# Flipper-Proto.net
KiCad netlist of a schematic drawn in EAGLE
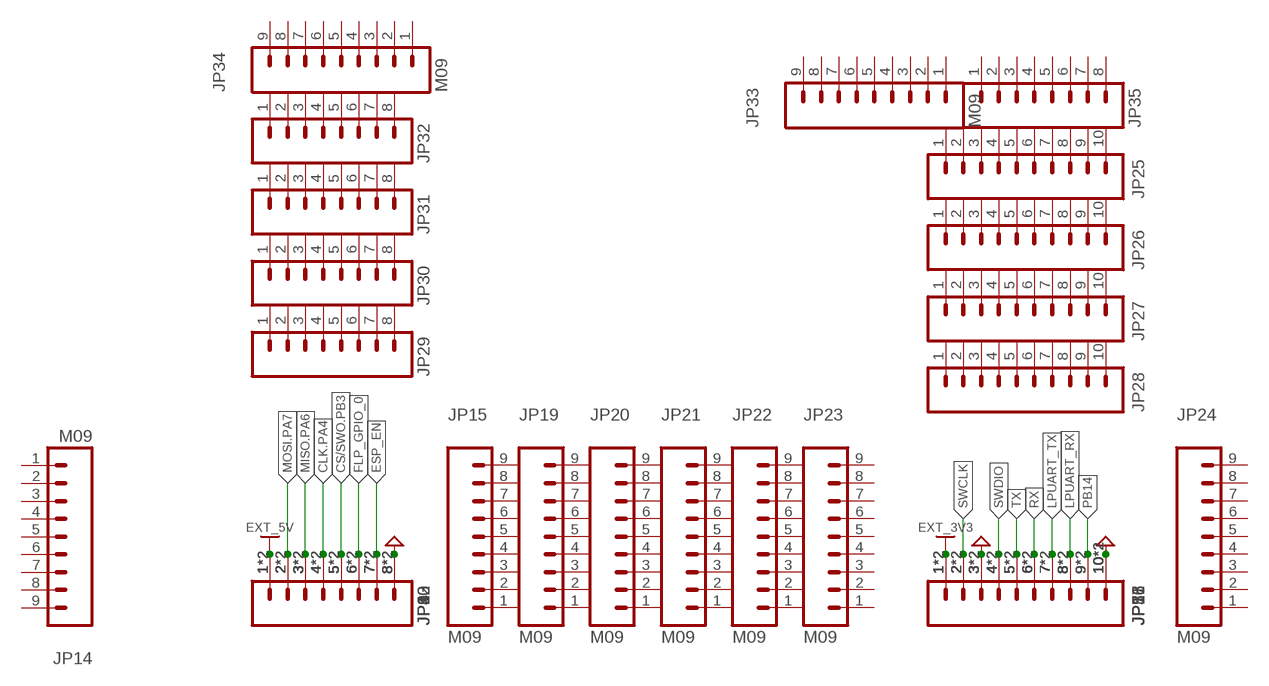
[diagram p0: schematic, sheet 1]

(export (version "E")
  (design (tool "Eeschema 10.0.6"))
  (components
    (comp (ref "JP1")
      (value "M10\"")
      (footprint "eagle-import:1X10")
      (libsource (lib "eagle-import") (part "M10{dblquote}"))
    )
    (comp (ref "JP2")
      (value "M08SMD-COMBO")
      (footprint "eagle-import:1X08_SMD_COMBINED")
      (libsource (lib "eagle-import") (part "M08SMD-COMBO"))
    )
    (comp (ref "JP3")
      (value "M08SMD-COMBO")
      (footprint "eagle-import:1X08_SMD_COMBINED")
      (libsource (lib "eagle-import") (part "M08SMD-COMBO"))
    )
    (comp (ref "JP4")
      (value "M08SMD-COMBO")
      (footprint "eagle-import:1X08_SMD_COMBINED")
      (libsource (lib "eagle-import") (part "M08SMD-COMBO"))
    )
    (comp (ref "JP5")
      (value "M10COMBINED")
      (footprint "eagle-import:1X10_SMD_COMBINED")
      (libsource (lib "eagle-import") (part "M10COMBINED"))
    )
    (comp (ref "JP6")
      (value "M081X08")
      (footprint "eagle-import:1X08")
      (libsource (lib "eagle-import") (part "M081X08"))
    )
    (comp (ref "JP7")
      (value "M10COMBINED")
      (footprint "eagle-import:1X10_SMD_COMBINED")
      (libsource (lib "eagle-import") (part "M10COMBINED"))
    )
    (comp (ref "JP8")
      (value "M10COMBINED")
      (footprint "eagle-import:1X10_SMD_COMBINED")
      (libsource (lib "eagle-import") (part "M10COMBINED"))
    )
    (comp (ref "JP9")
      (value "M081X08")
      (footprint "eagle-import:1X08")
      (libsource (lib "eagle-import") (part "M081X08"))
    )
    (comp (ref "JP10")
      (value "M081X08")
      (footprint "eagle-import:1X08")
      (libsource (lib "eagle-import") (part "M081X08"))
    )
    (comp (ref "JP11")
      (value "M10\"")
      (footprint "eagle-import:1X10")
      (libsource (lib "eagle-import") (part "M10{dblquote}"))
    )
    (comp (ref "JP12")
      (value "M081X08")
      (footprint "eagle-import:1X08")
      (libsource (lib "eagle-import") (part "M081X08"))
    )
    (comp (ref "JP13")
      (value "M081X08")
      (footprint "eagle-import:1X08")
      (libsource (lib "eagle-import") (part "M081X08"))
    )
    (comp (ref "JP14")
      (value "M09")
      (footprint "eagle-import:1X09")
      (libsource (lib "eagle-import") (part "M09"))
    )
    (comp (ref "JP15")
      (value "M09")
      (footprint "eagle-import:1X09")
      (libsource (lib "eagle-import") (part "M09"))
    )
    (comp (ref "JP16")
      (value "M10\"")
      (footprint "eagle-import:1X10")
      (libsource (lib "eagle-import") (part "M10{dblquote}"))
    )
    (comp (ref "JP17")
      (value "M10\"")
      (footprint "eagle-import:1X10")
      (libsource (lib "eagle-import") (part "M10{dblquote}"))
    )
    (comp (ref "JP18")
      (value "M10\"")
      (footprint "eagle-import:1X10")
      (libsource (lib "eagle-import") (part "M10{dblquote}"))
    )
    (comp (ref "JP19")
      (value "M09")
      (footprint "eagle-import:1X09")
      (libsource (lib "eagle-import") (part "M09"))
    )
    (comp (ref "JP20")
      (value "M09")
      (footprint "eagle-import:1X09")
      (libsource (lib "eagle-import") (part "M09"))
    )
    (comp (ref "JP21")
      (value "M09")
      (footprint "eagle-import:1X09")
      (libsource (lib "eagle-import") (part "M09"))
    )
    (comp (ref "JP22")
      (value "M09")
      (footprint "eagle-import:1X09")
      (libsource (lib "eagle-import") (part "M09"))
    )
    (comp (ref "JP23")
      (value "M09")
      (footprint "eagle-import:1X09")
      (libsource (lib "eagle-import") (part "M09"))
    )
    (comp (ref "JP24")
      (value "M09")
      (footprint "eagle-import:1X09")
      (libsource (lib "eagle-import") (part "M09"))
    )
    (comp (ref "JP25")
      (value "M10\"")
      (footprint "eagle-import:1X10")
      (libsource (lib "eagle-import") (part "M10{dblquote}"))
    )
    (comp (ref "JP26")
      (value "M10\"")
      (footprint "eagle-import:1X10")
      (libsource (lib "eagle-import") (part "M10{dblquote}"))
    )
    (comp (ref "JP27")
      (value "M10\"")
      (footprint "eagle-import:1X10")
      (libsource (lib "eagle-import") (part "M10{dblquote}"))
    )
    (comp (ref "JP28")
      (value "M10\"")
      (footprint "eagle-import:1X10")
      (libsource (lib "eagle-import") (part "M10{dblquote}"))
    )
    (comp (ref "JP29")
      (value "M081X08")
      (footprint "eagle-import:1X08")
      (libsource (lib "eagle-import") (part "M081X08"))
    )
    (comp (ref "JP30")
      (value "M081X08")
      (footprint "eagle-import:1X08")
      (libsource (lib "eagle-import") (part "M081X08"))
    )
    (comp (ref "JP31")
      (value "M081X08")
      (footprint "eagle-import:1X08")
      (libsource (lib "eagle-import") (part "M081X08"))
    )
    (comp (ref "JP32")
      (value "M081X08")
      (footprint "eagle-import:1X08")
      (libsource (lib "eagle-import") (part "M081X08"))
    )
    (comp (ref "JP33")
      (value "M09")
      (footprint "eagle-import:1X09")
      (libsource (lib "eagle-import") (part "M09"))
    )
    (comp (ref "JP34")
      (value "M09")
      (footprint "eagle-import:1X09")
      (libsource (lib "eagle-import") (part "M09"))
    )
    (comp (ref "JP35")
      (value "M081X08")
      (footprint "eagle-import:1X08")
      (libsource (lib "eagle-import") (part "M081X08"))
    )
  )
  (nets
    (net (code "1") (name "CLK.PA4") (class "Default")
      (node (ref "JP10") (pin "4") (pinfunction "4_4") (pintype "passive"))
      (node (ref "JP12") (pin "4") (pinfunction "4_4") (pintype "passive"))
      (node (ref "JP13") (pin "4") (pinfunction "4_4") (pintype "passive"))
      (node (ref "JP2") (pin "4") (pinfunction "4_4") (pintype "passive"))
      (node (ref "JP2") (pin "4@2") (pinfunction "4_4@2") (pintype "passive"))
      (node (ref "JP3") (pin "4") (pinfunction "4_4") (pintype "passive"))
      (node (ref "JP3") (pin "4@2") (pinfunction "4_4@2") (pintype "passive"))
      (node (ref "JP4") (pin "4") (pinfunction "4_4") (pintype "passive"))
      (node (ref "JP4") (pin "4@2") (pinfunction "4_4@2") (pintype "passive"))
      (node (ref "JP6") (pin "4") (pinfunction "4_4") (pintype "passive"))
      (node (ref "JP9") (pin "4") (pinfunction "4_4") (pintype "passive"))
    )
    (net (code "2") (name "CS{slash}SWO.PB3") (class "Default")
      (node (ref "JP10") (pin "5") (pinfunction "5_5") (pintype "passive"))
      (node (ref "JP12") (pin "5") (pinfunction "5_5") (pintype "passive"))
      (node (ref "JP13") (pin "5") (pinfunction "5_5") (pintype "passive"))
      (node (ref "JP2") (pin "5") (pinfunction "5_5") (pintype "passive"))
      (node (ref "JP2") (pin "5@2") (pinfunction "5_5@2") (pintype "passive"))
      (node (ref "JP3") (pin "5") (pinfunction "5_5") (pintype "passive"))
      (node (ref "JP3") (pin "5@2") (pinfunction "5_5@2") (pintype "passive"))
      (node (ref "JP4") (pin "5") (pinfunction "5_5") (pintype "passive"))
      (node (ref "JP4") (pin "5@2") (pinfunction "5_5@2") (pintype "passive"))
      (node (ref "JP6") (pin "5") (pinfunction "5_5") (pintype "passive"))
      (node (ref "JP9") (pin "5") (pinfunction "5_5") (pintype "passive"))
    )
    (net (code "3") (name "ESP_EN") (class "Default")
      (node (ref "JP10") (pin "7") (pinfunction "7_7") (pintype "passive"))
      (node (ref "JP12") (pin "7") (pinfunction "7_7") (pintype "passive"))
      (node (ref "JP13") (pin "7") (pinfunction "7_7") (pintype "passive"))
      (node (ref "JP2") (pin "7") (pinfunction "7_7") (pintype "passive"))
      (node (ref "JP2") (pin "7@2") (pinfunction "7_7@2") (pintype "passive"))
      (node (ref "JP3") (pin "7") (pinfunction "7_7") (pintype "passive"))
      (node (ref "JP3") (pin "7@2") (pinfunction "7_7@2") (pintype "passive"))
      (node (ref "JP4") (pin "7") (pinfunction "7_7") (pintype "passive"))
      (node (ref "JP4") (pin "7@2") (pinfunction "7_7@2") (pintype "passive"))
      (node (ref "JP6") (pin "7") (pinfunction "7_7") (pintype "passive"))
      (node (ref "JP9") (pin "7") (pinfunction "7_7") (pintype "passive"))
    )
    (net (code "4") (name "EXT_3V3") (class "Default")
      (node (ref "JP1") (pin "1") (pinfunction "1_1") (pintype "passive"))
      (node (ref "JP11") (pin "1") (pinfunction "1_1") (pintype "passive"))
      (node (ref "JP16") (pin "1") (pinfunction "1_1") (pintype "passive"))
      (node (ref "JP17") (pin "1") (pinfunction "1_1") (pintype "passive"))
      (node (ref "JP18") (pin "1") (pinfunction "1_1") (pintype "passive"))
      (node (ref "JP5") (pin "1") (pinfunction "1_1") (pintype "passive"))
      (node (ref "JP5") (pin "1@2") (pinfunction "1_1@2") (pintype "passive"))
      (node (ref "JP7") (pin "1") (pinfunction "1_1") (pintype "passive"))
      (node (ref "JP7") (pin "1@2") (pinfunction "1_1@2") (pintype "passive"))
      (node (ref "JP8") (pin "1") (pinfunction "1_1") (pintype "passive"))
      (node (ref "JP8") (pin "1@2") (pinfunction "1_1@2") (pintype "passive"))
    )
    (net (code "5") (name "EXT_5V") (class "Default")
      (node (ref "JP10") (pin "1") (pinfunction "1_1") (pintype "passive"))
      (node (ref "JP12") (pin "1") (pinfunction "1_1") (pintype "passive"))
      (node (ref "JP13") (pin "1") (pinfunction "1_1") (pintype "passive"))
      (node (ref "JP2") (pin "1") (pinfunction "1_1") (pintype "passive"))
      (node (ref "JP2") (pin "1@2") (pinfunction "1_1@2") (pintype "passive"))
      (node (ref "JP3") (pin "1") (pinfunction "1_1") (pintype "passive"))
      (node (ref "JP3") (pin "1@2") (pinfunction "1_1@2") (pintype "passive"))
      (node (ref "JP4") (pin "1") (pinfunction "1_1") (pintype "passive"))
      (node (ref "JP4") (pin "1@2") (pinfunction "1_1@2") (pintype "passive"))
      (node (ref "JP6") (pin "1") (pinfunction "1_1") (pintype "passive"))
      (node (ref "JP9") (pin "1") (pinfunction "1_1") (pintype "passive"))
    )
    (net (code "6") (name "FLP_GPIO_0") (class "Default")
      (node (ref "JP10") (pin "6") (pinfunction "6_6") (pintype "passive"))
      (node (ref "JP12") (pin "6") (pinfunction "6_6") (pintype "passive"))
      (node (ref "JP13") (pin "6") (pinfunction "6_6") (pintype "passive"))
      (node (ref "JP2") (pin "6") (pinfunction "6_6") (pintype "passive"))
      (node (ref "JP2") (pin "6@2") (pinfunction "6_6@2") (pintype "passive"))
      (node (ref "JP3") (pin "6") (pinfunction "6_6") (pintype "passive"))
      (node (ref "JP3") (pin "6@2") (pinfunction "6_6@2") (pintype "passive"))
      (node (ref "JP4") (pin "6") (pinfunction "6_6") (pintype "passive"))
      (node (ref "JP4") (pin "6@2") (pinfunction "6_6@2") (pintype "passive"))
      (node (ref "JP6") (pin "6") (pinfunction "6_6") (pintype "passive"))
      (node (ref "JP9") (pin "6") (pinfunction "6_6") (pintype "passive"))
    )
    (net (code "7") (name "GND") (class "Default")
      (node (ref "JP1") (pin "10") (pinfunction "10_10") (pintype "passive"))
      (node (ref "JP1") (pin "3") (pinfunction "3_3") (pintype "passive"))
      (node (ref "JP10") (pin "8") (pinfunction "8_8") (pintype "passive"))
      (node (ref "JP11") (pin "10") (pinfunction "10_10") (pintype "passive"))
      (node (ref "JP11") (pin "3") (pinfunction "3_3") (pintype "passive"))
      (node (ref "JP12") (pin "8") (pinfunction "8_8") (pintype "passive"))
      (node (ref "JP13") (pin "8") (pinfunction "8_8") (pintype "passive"))
      (node (ref "JP16") (pin "10") (pinfunction "10_10") (pintype "passive"))
      (node (ref "JP16") (pin "3") (pinfunction "3_3") (pintype "passive"))
      (node (ref "JP17") (pin "10") (pinfunction "10_10") (pintype "passive"))
      (node (ref "JP17") (pin "3") (pinfunction "3_3") (pintype "passive"))
      (node (ref "JP18") (pin "10") (pinfunction "10_10") (pintype "passive"))
      (node (ref "JP18") (pin "3") (pinfunction "3_3") (pintype "passive"))
      (node (ref "JP2") (pin "8") (pinfunction "8_8") (pintype "passive"))
      (node (ref "JP2") (pin "8@2") (pinfunction "8_8@2") (pintype "passive"))
      (node (ref "JP3") (pin "8") (pinfunction "8_8") (pintype "passive"))
      (node (ref "JP3") (pin "8@2") (pinfunction "8_8@2") (pintype "passive"))
      (node (ref "JP4") (pin "8") (pinfunction "8_8") (pintype "passive"))
      (node (ref "JP4") (pin "8@2") (pinfunction "8_8@2") (pintype "passive"))
      (node (ref "JP5") (pin "10") (pinfunction "10_10") (pintype "passive"))
      (node (ref "JP5") (pin "10@2") (pinfunction "10_10@2") (pintype "passive"))
      (node (ref "JP5") (pin "3") (pinfunction "3_3") (pintype "passive"))
      (node (ref "JP5") (pin "3@2") (pinfunction "3_3@2") (pintype "passive"))
      (node (ref "JP6") (pin "8") (pinfunction "8_8") (pintype "passive"))
      (node (ref "JP7") (pin "10") (pinfunction "10_10") (pintype "passive"))
      (node (ref "JP7") (pin "10@2") (pinfunction "10_10@2") (pintype "passive"))
      (node (ref "JP7") (pin "3") (pinfunction "3_3") (pintype "passive"))
      (node (ref "JP7") (pin "3@2") (pinfunction "3_3@2") (pintype "passive"))
      (node (ref "JP8") (pin "10") (pinfunction "10_10") (pintype "passive"))
      (node (ref "JP8") (pin "10@2") (pinfunction "10_10@2") (pintype "passive"))
      (node (ref "JP8") (pin "3") (pinfunction "3_3") (pintype "passive"))
      (node (ref "JP8") (pin "3@2") (pinfunction "3_3@2") (pintype "passive"))
      (node (ref "JP9") (pin "8") (pinfunction "8_8") (pintype "passive"))
    )
    (net (code "8") (name "LPUART_RX") (class "Default")
      (node (ref "JP1") (pin "8") (pinfunction "8_8") (pintype "passive"))
      (node (ref "JP11") (pin "8") (pinfunction "8_8") (pintype "passive"))
      (node (ref "JP16") (pin "8") (pinfunction "8_8") (pintype "passive"))
      (node (ref "JP17") (pin "8") (pinfunction "8_8") (pintype "passive"))
      (node (ref "JP18") (pin "8") (pinfunction "8_8") (pintype "passive"))
      (node (ref "JP5") (pin "8") (pinfunction "8_8") (pintype "passive"))
      (node (ref "JP5") (pin "8@2") (pinfunction "8_8@2") (pintype "passive"))
      (node (ref "JP7") (pin "8") (pinfunction "8_8") (pintype "passive"))
      (node (ref "JP7") (pin "8@2") (pinfunction "8_8@2") (pintype "passive"))
      (node (ref "JP8") (pin "8") (pinfunction "8_8") (pintype "passive"))
      (node (ref "JP8") (pin "8@2") (pinfunction "8_8@2") (pintype "passive"))
    )
    (net (code "9") (name "LPUART_TX") (class "Default")
      (node (ref "JP1") (pin "7") (pinfunction "7_7") (pintype "passive"))
      (node (ref "JP11") (pin "7") (pinfunction "7_7") (pintype "passive"))
      (node (ref "JP16") (pin "7") (pinfunction "7_7") (pintype "passive"))
      (node (ref "JP17") (pin "7") (pinfunction "7_7") (pintype "passive"))
      (node (ref "JP18") (pin "7") (pinfunction "7_7") (pintype "passive"))
      (node (ref "JP5") (pin "7") (pinfunction "7_7") (pintype "passive"))
      (node (ref "JP5") (pin "7@2") (pinfunction "7_7@2") (pintype "passive"))
      (node (ref "JP7") (pin "7") (pinfunction "7_7") (pintype "passive"))
      (node (ref "JP7") (pin "7@2") (pinfunction "7_7@2") (pintype "passive"))
      (node (ref "JP8") (pin "7") (pinfunction "7_7") (pintype "passive"))
      (node (ref "JP8") (pin "7@2") (pinfunction "7_7@2") (pintype "passive"))
    )
    (net (code "10") (name "MISO.PA6") (class "Default")
      (node (ref "JP10") (pin "3") (pinfunction "3_3") (pintype "passive"))
      (node (ref "JP12") (pin "3") (pinfunction "3_3") (pintype "passive"))
      (node (ref "JP13") (pin "3") (pinfunction "3_3") (pintype "passive"))
      (node (ref "JP2") (pin "3") (pinfunction "3_3") (pintype "passive"))
      (node (ref "JP2") (pin "3@2") (pinfunction "3_3@2") (pintype "passive"))
      (node (ref "JP3") (pin "3") (pinfunction "3_3") (pintype "passive"))
      (node (ref "JP3") (pin "3@2") (pinfunction "3_3@2") (pintype "passive"))
      (node (ref "JP4") (pin "3") (pinfunction "3_3") (pintype "passive"))
      (node (ref "JP4") (pin "3@2") (pinfunction "3_3@2") (pintype "passive"))
      (node (ref "JP6") (pin "3") (pinfunction "3_3") (pintype "passive"))
      (node (ref "JP9") (pin "3") (pinfunction "3_3") (pintype "passive"))
    )
    (net (code "11") (name "MOSI.PA7") (class "Default")
      (node (ref "JP10") (pin "2") (pinfunction "2_2") (pintype "passive"))
      (node (ref "JP12") (pin "2") (pinfunction "2_2") (pintype "passive"))
      (node (ref "JP13") (pin "2") (pinfunction "2_2") (pintype "passive"))
      (node (ref "JP2") (pin "2") (pinfunction "2_2") (pintype "passive"))
      (node (ref "JP2") (pin "2@2") (pinfunction "2_2@2") (pintype "passive"))
      (node (ref "JP3") (pin "2") (pinfunction "2_2") (pintype "passive"))
      (node (ref "JP3") (pin "2@2") (pinfunction "2_2@2") (pintype "passive"))
      (node (ref "JP4") (pin "2") (pinfunction "2_2") (pintype "passive"))
      (node (ref "JP4") (pin "2@2") (pinfunction "2_2@2") (pintype "passive"))
      (node (ref "JP6") (pin "2") (pinfunction "2_2") (pintype "passive"))
      (node (ref "JP9") (pin "2") (pinfunction "2_2") (pintype "passive"))
    )
    (net (code "12") (name "PB14") (class "Default")
      (node (ref "JP1") (pin "9") (pinfunction "9_9") (pintype "passive"))
      (node (ref "JP11") (pin "9") (pinfunction "9_9") (pintype "passive"))
      (node (ref "JP16") (pin "9") (pinfunction "9_9") (pintype "passive"))
      (node (ref "JP17") (pin "9") (pinfunction "9_9") (pintype "passive"))
      (node (ref "JP18") (pin "9") (pinfunction "9_9") (pintype "passive"))
      (node (ref "JP5") (pin "9") (pinfunction "9_9") (pintype "passive"))
      (node (ref "JP5") (pin "9@2") (pinfunction "9_9@2") (pintype "passive"))
      (node (ref "JP7") (pin "9") (pinfunction "9_9") (pintype "passive"))
      (node (ref "JP7") (pin "9@2") (pinfunction "9_9@2") (pintype "passive"))
      (node (ref "JP8") (pin "9") (pinfunction "9_9") (pintype "passive"))
      (node (ref "JP8") (pin "9@2") (pinfunction "9_9@2") (pintype "passive"))
    )
    (net (code "13") (name "RX") (class "Default")
      (node (ref "JP1") (pin "6") (pinfunction "6_6") (pintype "passive"))
      (node (ref "JP11") (pin "6") (pinfunction "6_6") (pintype "passive"))
      (node (ref "JP16") (pin "6") (pinfunction "6_6") (pintype "passive"))
      (node (ref "JP17") (pin "6") (pinfunction "6_6") (pintype "passive"))
      (node (ref "JP18") (pin "6") (pinfunction "6_6") (pintype "passive"))
      (node (ref "JP5") (pin "6") (pinfunction "6_6") (pintype "passive"))
      (node (ref "JP5") (pin "6@2") (pinfunction "6_6@2") (pintype "passive"))
      (node (ref "JP7") (pin "6") (pinfunction "6_6") (pintype "passive"))
      (node (ref "JP7") (pin "6@2") (pinfunction "6_6@2") (pintype "passive"))
      (node (ref "JP8") (pin "6") (pinfunction "6_6") (pintype "passive"))
      (node (ref "JP8") (pin "6@2") (pinfunction "6_6@2") (pintype "passive"))
    )
    (net (code "14") (name "SWCLK") (class "Default")
      (node (ref "JP1") (pin "2") (pinfunction "2_2") (pintype "passive"))
      (node (ref "JP11") (pin "2") (pinfunction "2_2") (pintype "passive"))
      (node (ref "JP16") (pin "2") (pinfunction "2_2") (pintype "passive"))
      (node (ref "JP17") (pin "2") (pinfunction "2_2") (pintype "passive"))
      (node (ref "JP18") (pin "2") (pinfunction "2_2") (pintype "passive"))
      (node (ref "JP5") (pin "2") (pinfunction "2_2") (pintype "passive"))
      (node (ref "JP5") (pin "2@2") (pinfunction "2_2@2") (pintype "passive"))
      (node (ref "JP7") (pin "2") (pinfunction "2_2") (pintype "passive"))
      (node (ref "JP7") (pin "2@2") (pinfunction "2_2@2") (pintype "passive"))
      (node (ref "JP8") (pin "2") (pinfunction "2_2") (pintype "passive"))
      (node (ref "JP8") (pin "2@2") (pinfunction "2_2@2") (pintype "passive"))
    )
    (net (code "15") (name "SWDIO") (class "Default")
      (node (ref "JP1") (pin "4") (pinfunction "4_4") (pintype "passive"))
      (node (ref "JP11") (pin "4") (pinfunction "4_4") (pintype "passive"))
      (node (ref "JP16") (pin "4") (pinfunction "4_4") (pintype "passive"))
      (node (ref "JP17") (pin "4") (pinfunction "4_4") (pintype "passive"))
      (node (ref "JP18") (pin "4") (pinfunction "4_4") (pintype "passive"))
      (node (ref "JP5") (pin "4") (pinfunction "4_4") (pintype "passive"))
      (node (ref "JP5") (pin "4@2") (pinfunction "4_4@2") (pintype "passive"))
      (node (ref "JP7") (pin "4") (pinfunction "4_4") (pintype "passive"))
      (node (ref "JP7") (pin "4@2") (pinfunction "4_4@2") (pintype "passive"))
      (node (ref "JP8") (pin "4") (pinfunction "4_4") (pintype "passive"))
      (node (ref "JP8") (pin "4@2") (pinfunction "4_4@2") (pintype "passive"))
    )
    (net (code "16") (name "TX") (class "Default")
      (node (ref "JP1") (pin "5") (pinfunction "5_5") (pintype "passive"))
      (node (ref "JP11") (pin "5") (pinfunction "5_5") (pintype "passive"))
      (node (ref "JP16") (pin "5") (pinfunction "5_5") (pintype "passive"))
      (node (ref "JP17") (pin "5") (pinfunction "5_5") (pintype "passive"))
      (node (ref "JP18") (pin "5") (pinfunction "5_5") (pintype "passive"))
      (node (ref "JP5") (pin "5") (pinfunction "5_5") (pintype "passive"))
      (node (ref "JP5") (pin "5@2") (pinfunction "5_5@2") (pintype "passive"))
      (node (ref "JP7") (pin "5") (pinfunction "5_5") (pintype "passive"))
      (node (ref "JP7") (pin "5@2") (pinfunction "5_5@2") (pintype "passive"))
      (node (ref "JP8") (pin "5") (pinfunction "5_5") (pintype "passive"))
      (node (ref "JP8") (pin "5@2") (pinfunction "5_5@2") (pintype "passive"))
    )
    (net (code "17") (name "unconnected-(JP14-Pad1)") (class "Default")
      (node (ref "JP14") (pin "1") (pinfunction "1_1") (pintype "passive"))
    )
    (net (code "18") (name "unconnected-(JP14-Pad2)") (class "Default")
      (node (ref "JP14") (pin "2") (pinfunction "2_2") (pintype "passive"))
    )
    (net (code "19") (name "unconnected-(JP14-Pad3)") (class "Default")
      (node (ref "JP14") (pin "3") (pinfunction "3_3") (pintype "passive"))
    )
    (net (code "20") (name "unconnected-(JP14-Pad4)") (class "Default")
      (node (ref "JP14") (pin "4") (pinfunction "4_4") (pintype "passive"))
    )
    (net (code "21") (name "unconnected-(JP14-Pad5)") (class "Default")
      (node (ref "JP14") (pin "5") (pinfunction "5_5") (pintype "passive"))
    )
    (net (code "22") (name "unconnected-(JP14-Pad6)") (class "Default")
      (node (ref "JP14") (pin "6") (pinfunction "6_6") (pintype "passive"))
    )
    (net (code "23") (name "unconnected-(JP14-Pad7)") (class "Default")
      (node (ref "JP14") (pin "7") (pinfunction "7_7") (pintype "passive"))
    )
    (net (code "24") (name "unconnected-(JP14-Pad8)") (class "Default")
      (node (ref "JP14") (pin "8") (pinfunction "8_8") (pintype "passive"))
    )
    (net (code "25") (name "unconnected-(JP14-Pad9)") (class "Default")
      (node (ref "JP14") (pin "9") (pinfunction "9_9") (pintype "passive"))
    )
    (net (code "26") (name "unconnected-(JP15-Pad1)") (class "Default")
      (node (ref "JP15") (pin "1") (pinfunction "1_1") (pintype "passive"))
    )
    (net (code "27") (name "unconnected-(JP15-Pad2)") (class "Default")
      (node (ref "JP15") (pin "2") (pinfunction "2_2") (pintype "passive"))
    )
    (net (code "28") (name "unconnected-(JP15-Pad3)") (class "Default")
      (node (ref "JP15") (pin "3") (pinfunction "3_3") (pintype "passive"))
    )
    (net (code "29") (name "unconnected-(JP15-Pad4)") (class "Default")
      (node (ref "JP15") (pin "4") (pinfunction "4_4") (pintype "passive"))
    )
    (net (code "30") (name "unconnected-(JP15-Pad5)") (class "Default")
      (node (ref "JP15") (pin "5") (pinfunction "5_5") (pintype "passive"))
    )
    (net (code "31") (name "unconnected-(JP15-Pad6)") (class "Default")
      (node (ref "JP15") (pin "6") (pinfunction "6_6") (pintype "passive"))
    )
    (net (code "32") (name "unconnected-(JP15-Pad7)") (class "Default")
      (node (ref "JP15") (pin "7") (pinfunction "7_7") (pintype "passive"))
    )
    (net (code "33") (name "unconnected-(JP15-Pad8)") (class "Default")
      (node (ref "JP15") (pin "8") (pinfunction "8_8") (pintype "passive"))
    )
    (net (code "34") (name "unconnected-(JP15-Pad9)") (class "Default")
      (node (ref "JP15") (pin "9") (pinfunction "9_9") (pintype "passive"))
    )
    (net (code "35") (name "unconnected-(JP19-Pad1)") (class "Default")
      (node (ref "JP19") (pin "1") (pinfunction "1_1") (pintype "passive"))
    )
    (net (code "36") (name "unconnected-(JP19-Pad2)") (class "Default")
      (node (ref "JP19") (pin "2") (pinfunction "2_2") (pintype "passive"))
    )
    (net (code "37") (name "unconnected-(JP19-Pad3)") (class "Default")
      (node (ref "JP19") (pin "3") (pinfunction "3_3") (pintype "passive"))
    )
    (net (code "38") (name "unconnected-(JP19-Pad4)") (class "Default")
      (node (ref "JP19") (pin "4") (pinfunction "4_4") (pintype "passive"))
    )
    (net (code "39") (name "unconnected-(JP19-Pad5)") (class "Default")
      (node (ref "JP19") (pin "5") (pinfunction "5_5") (pintype "passive"))
    )
    (net (code "40") (name "unconnected-(JP19-Pad6)") (class "Default")
      (node (ref "JP19") (pin "6") (pinfunction "6_6") (pintype "passive"))
    )
    (net (code "41") (name "unconnected-(JP19-Pad7)") (class "Default")
      (node (ref "JP19") (pin "7") (pinfunction "7_7") (pintype "passive"))
    )
    (net (code "42") (name "unconnected-(JP19-Pad8)") (class "Default")
      (node (ref "JP19") (pin "8") (pinfunction "8_8") (pintype "passive"))
    )
    (net (code "43") (name "unconnected-(JP19-Pad9)") (class "Default")
      (node (ref "JP19") (pin "9") (pinfunction "9_9") (pintype "passive"))
    )
    (net (code "44") (name "unconnected-(JP20-Pad1)") (class "Default")
      (node (ref "JP20") (pin "1") (pinfunction "1_1") (pintype "passive"))
    )
    (net (code "45") (name "unconnected-(JP20-Pad2)") (class "Default")
      (node (ref "JP20") (pin "2") (pinfunction "2_2") (pintype "passive"))
    )
    (net (code "46") (name "unconnected-(JP20-Pad3)") (class "Default")
      (node (ref "JP20") (pin "3") (pinfunction "3_3") (pintype "passive"))
    )
    (net (code "47") (name "unconnected-(JP20-Pad4)") (class "Default")
      (node (ref "JP20") (pin "4") (pinfunction "4_4") (pintype "passive"))
    )
    (net (code "48") (name "unconnected-(JP20-Pad5)") (class "Default")
      (node (ref "JP20") (pin "5") (pinfunction "5_5") (pintype "passive"))
    )
    (net (code "49") (name "unconnected-(JP20-Pad6)") (class "Default")
      (node (ref "JP20") (pin "6") (pinfunction "6_6") (pintype "passive"))
    )
    (net (code "50") (name "unconnected-(JP20-Pad7)") (class "Default")
      (node (ref "JP20") (pin "7") (pinfunction "7_7") (pintype "passive"))
    )
    (net (code "51") (name "unconnected-(JP20-Pad8)") (class "Default")
      (node (ref "JP20") (pin "8") (pinfunction "8_8") (pintype "passive"))
    )
    (net (code "52") (name "unconnected-(JP20-Pad9)") (class "Default")
      (node (ref "JP20") (pin "9") (pinfunction "9_9") (pintype "passive"))
    )
    (net (code "53") (name "unconnected-(JP21-Pad1)") (class "Default")
      (node (ref "JP21") (pin "1") (pinfunction "1_1") (pintype "passive"))
    )
    (net (code "54") (name "unconnected-(JP21-Pad2)") (class "Default")
      (node (ref "JP21") (pin "2") (pinfunction "2_2") (pintype "passive"))
    )
    (net (code "55") (name "unconnected-(JP21-Pad3)") (class "Default")
      (node (ref "JP21") (pin "3") (pinfunction "3_3") (pintype "passive"))
    )
    (net (code "56") (name "unconnected-(JP21-Pad4)") (class "Default")
      (node (ref "JP21") (pin "4") (pinfunction "4_4") (pintype "passive"))
    )
    (net (code "57") (name "unconnected-(JP21-Pad5)") (class "Default")
      (node (ref "JP21") (pin "5") (pinfunction "5_5") (pintype "passive"))
    )
    (net (code "58") (name "unconnected-(JP21-Pad6)") (class "Default")
      (node (ref "JP21") (pin "6") (pinfunction "6_6") (pintype "passive"))
    )
    (net (code "59") (name "unconnected-(JP21-Pad7)") (class "Default")
      (node (ref "JP21") (pin "7") (pinfunction "7_7") (pintype "passive"))
    )
    (net (code "60") (name "unconnected-(JP21-Pad8)") (class "Default")
      (node (ref "JP21") (pin "8") (pinfunction "8_8") (pintype "passive"))
    )
    (net (code "61") (name "unconnected-(JP21-Pad9)") (class "Default")
      (node (ref "JP21") (pin "9") (pinfunction "9_9") (pintype "passive"))
    )
    (net (code "62") (name "unconnected-(JP22-Pad1)") (class "Default")
      (node (ref "JP22") (pin "1") (pinfunction "1_1") (pintype "passive"))
    )
    (net (code "63") (name "unconnected-(JP22-Pad2)") (class "Default")
      (node (ref "JP22") (pin "2") (pinfunction "2_2") (pintype "passive"))
    )
    (net (code "64") (name "unconnected-(JP22-Pad3)") (class "Default")
      (node (ref "JP22") (pin "3") (pinfunction "3_3") (pintype "passive"))
    )
    (net (code "65") (name "unconnected-(JP22-Pad4)") (class "Default")
      (node (ref "JP22") (pin "4") (pinfunction "4_4") (pintype "passive"))
    )
    (net (code "66") (name "unconnected-(JP22-Pad5)") (class "Default")
      (node (ref "JP22") (pin "5") (pinfunction "5_5") (pintype "passive"))
    )
    (net (code "67") (name "unconnected-(JP22-Pad6)") (class "Default")
      (node (ref "JP22") (pin "6") (pinfunction "6_6") (pintype "passive"))
    )
    (net (code "68") (name "unconnected-(JP22-Pad7)") (class "Default")
      (node (ref "JP22") (pin "7") (pinfunction "7_7") (pintype "passive"))
    )
    (net (code "69") (name "unconnected-(JP22-Pad8)") (class "Default")
      (node (ref "JP22") (pin "8") (pinfunction "8_8") (pintype "passive"))
    )
    (net (code "70") (name "unconnected-(JP22-Pad9)") (class "Default")
      (node (ref "JP22") (pin "9") (pinfunction "9_9") (pintype "passive"))
    )
    (net (code "71") (name "unconnected-(JP23-Pad1)") (class "Default")
      (node (ref "JP23") (pin "1") (pinfunction "1_1") (pintype "passive"))
    )
    (net (code "72") (name "unconnected-(JP23-Pad2)") (class "Default")
      (node (ref "JP23") (pin "2") (pinfunction "2_2") (pintype "passive"))
    )
    (net (code "73") (name "unconnected-(JP23-Pad3)") (class "Default")
      (node (ref "JP23") (pin "3") (pinfunction "3_3") (pintype "passive"))
    )
    (net (code "74") (name "unconnected-(JP23-Pad4)") (class "Default")
      (node (ref "JP23") (pin "4") (pinfunction "4_4") (pintype "passive"))
    )
    (net (code "75") (name "unconnected-(JP23-Pad5)") (class "Default")
      (node (ref "JP23") (pin "5") (pinfunction "5_5") (pintype "passive"))
    )
    (net (code "76") (name "unconnected-(JP23-Pad6)") (class "Default")
      (node (ref "JP23") (pin "6") (pinfunction "6_6") (pintype "passive"))
    )
    (net (code "77") (name "unconnected-(JP23-Pad7)") (class "Default")
      (node (ref "JP23") (pin "7") (pinfunction "7_7") (pintype "passive"))
    )
    (net (code "78") (name "unconnected-(JP23-Pad8)") (class "Default")
      (node (ref "JP23") (pin "8") (pinfunction "8_8") (pintype "passive"))
    )
    (net (code "79") (name "unconnected-(JP23-Pad9)") (class "Default")
      (node (ref "JP23") (pin "9") (pinfunction "9_9") (pintype "passive"))
    )
    (net (code "80") (name "unconnected-(JP24-Pad1)") (class "Default")
      (node (ref "JP24") (pin "1") (pinfunction "1_1") (pintype "passive"))
    )
    (net (code "81") (name "unconnected-(JP24-Pad2)") (class "Default")
      (node (ref "JP24") (pin "2") (pinfunction "2_2") (pintype "passive"))
    )
    (net (code "82") (name "unconnected-(JP24-Pad3)") (class "Default")
      (node (ref "JP24") (pin "3") (pinfunction "3_3") (pintype "passive"))
    )
    (net (code "83") (name "unconnected-(JP24-Pad4)") (class "Default")
      (node (ref "JP24") (pin "4") (pinfunction "4_4") (pintype "passive"))
    )
    (net (code "84") (name "unconnected-(JP24-Pad5)") (class "Default")
      (node (ref "JP24") (pin "5") (pinfunction "5_5") (pintype "passive"))
    )
    (net (code "85") (name "unconnected-(JP24-Pad6)") (class "Default")
      (node (ref "JP24") (pin "6") (pinfunction "6_6") (pintype "passive"))
    )
    (net (code "86") (name "unconnected-(JP24-Pad7)") (class "Default")
      (node (ref "JP24") (pin "7") (pinfunction "7_7") (pintype "passive"))
    )
    (net (code "87") (name "unconnected-(JP24-Pad8)") (class "Default")
      (node (ref "JP24") (pin "8") (pinfunction "8_8") (pintype "passive"))
    )
    (net (code "88") (name "unconnected-(JP24-Pad9)") (class "Default")
      (node (ref "JP24") (pin "9") (pinfunction "9_9") (pintype "passive"))
    )
    (net (code "89") (name "unconnected-(JP25-Pad1)") (class "Default")
      (node (ref "JP25") (pin "1") (pinfunction "1_1") (pintype "passive"))
    )
    (net (code "90") (name "unconnected-(JP25-Pad2)") (class "Default")
      (node (ref "JP25") (pin "2") (pinfunction "2_2") (pintype "passive"))
    )
    (net (code "91") (name "unconnected-(JP25-Pad3)") (class "Default")
      (node (ref "JP25") (pin "3") (pinfunction "3_3") (pintype "passive"))
    )
    (net (code "92") (name "unconnected-(JP25-Pad4)") (class "Default")
      (node (ref "JP25") (pin "4") (pinfunction "4_4") (pintype "passive"))
    )
    (net (code "93") (name "unconnected-(JP25-Pad5)") (class "Default")
      (node (ref "JP25") (pin "5") (pinfunction "5_5") (pintype "passive"))
    )
    (net (code "94") (name "unconnected-(JP25-Pad6)") (class "Default")
      (node (ref "JP25") (pin "6") (pinfunction "6_6") (pintype "passive"))
    )
    (net (code "95") (name "unconnected-(JP25-Pad7)") (class "Default")
      (node (ref "JP25") (pin "7") (pinfunction "7_7") (pintype "passive"))
    )
    (net (code "96") (name "unconnected-(JP25-Pad8)") (class "Default")
      (node (ref "JP25") (pin "8") (pinfunction "8_8") (pintype "passive"))
    )
    (net (code "97") (name "unconnected-(JP25-Pad9)") (class "Default")
      (node (ref "JP25") (pin "9") (pinfunction "9_9") (pintype "passive"))
    )
    (net (code "98") (name "unconnected-(JP25-Pad10)") (class "Default")
      (node (ref "JP25") (pin "10") (pinfunction "10_10") (pintype "passive"))
    )
    (net (code "99") (name "unconnected-(JP26-Pad1)") (class "Default")
      (node (ref "JP26") (pin "1") (pinfunction "1_1") (pintype "passive"))
    )
    (net (code "100") (name "unconnected-(JP26-Pad2)") (class "Default")
      (node (ref "JP26") (pin "2") (pinfunction "2_2") (pintype "passive"))
    )
    (net (code "101") (name "unconnected-(JP26-Pad3)") (class "Default")
      (node (ref "JP26") (pin "3") (pinfunction "3_3") (pintype "passive"))
    )
    (net (code "102") (name "unconnected-(JP26-Pad4)") (class "Default")
      (node (ref "JP26") (pin "4") (pinfunction "4_4") (pintype "passive"))
    )
    (net (code "103") (name "unconnected-(JP26-Pad5)") (class "Default")
      (node (ref "JP26") (pin "5") (pinfunction "5_5") (pintype "passive"))
    )
    (net (code "104") (name "unconnected-(JP26-Pad6)") (class "Default")
      (node (ref "JP26") (pin "6") (pinfunction "6_6") (pintype "passive"))
    )
    (net (code "105") (name "unconnected-(JP26-Pad7)") (class "Default")
      (node (ref "JP26") (pin "7") (pinfunction "7_7") (pintype "passive"))
    )
    (net (code "106") (name "unconnected-(JP26-Pad8)") (class "Default")
      (node (ref "JP26") (pin "8") (pinfunction "8_8") (pintype "passive"))
    )
    (net (code "107") (name "unconnected-(JP26-Pad9)") (class "Default")
      (node (ref "JP26") (pin "9") (pinfunction "9_9") (pintype "passive"))
    )
    (net (code "108") (name "unconnected-(JP26-Pad10)") (class "Default")
      (node (ref "JP26") (pin "10") (pinfunction "10_10") (pintype "passive"))
    )
    (net (code "109") (name "unconnected-(JP27-Pad1)") (class "Default")
      (node (ref "JP27") (pin "1") (pinfunction "1_1") (pintype "passive"))
    )
    (net (code "110") (name "unconnected-(JP27-Pad2)") (class "Default")
      (node (ref "JP27") (pin "2") (pinfunction "2_2") (pintype "passive"))
    )
    (net (code "111") (name "unconnected-(JP27-Pad3)") (class "Default")
      (node (ref "JP27") (pin "3") (pinfunction "3_3") (pintype "passive"))
    )
    (net (code "112") (name "unconnected-(JP27-Pad4)") (class "Default")
      (node (ref "JP27") (pin "4") (pinfunction "4_4") (pintype "passive"))
    )
    (net (code "113") (name "unconnected-(JP27-Pad5)") (class "Default")
      (node (ref "JP27") (pin "5") (pinfunction "5_5") (pintype "passive"))
    )
    (net (code "114") (name "unconnected-(JP27-Pad6)") (class "Default")
      (node (ref "JP27") (pin "6") (pinfunction "6_6") (pintype "passive"))
    )
    (net (code "115") (name "unconnected-(JP27-Pad7)") (class "Default")
      (node (ref "JP27") (pin "7") (pinfunction "7_7") (pintype "passive"))
    )
    (net (code "116") (name "unconnected-(JP27-Pad8)") (class "Default")
      (node (ref "JP27") (pin "8") (pinfunction "8_8") (pintype "passive"))
    )
    (net (code "117") (name "unconnected-(JP27-Pad9)") (class "Default")
      (node (ref "JP27") (pin "9") (pinfunction "9_9") (pintype "passive"))
    )
    (net (code "118") (name "unconnected-(JP27-Pad10)") (class "Default")
      (node (ref "JP27") (pin "10") (pinfunction "10_10") (pintype "passive"))
    )
    (net (code "119") (name "unconnected-(JP28-Pad1)") (class "Default")
      (node (ref "JP28") (pin "1") (pinfunction "1_1") (pintype "passive"))
    )
    (net (code "120") (name "unconnected-(JP28-Pad2)") (class "Default")
      (node (ref "JP28") (pin "2") (pinfunction "2_2") (pintype "passive"))
    )
    (net (code "121") (name "unconnected-(JP28-Pad3)") (class "Default")
      (node (ref "JP28") (pin "3") (pinfunction "3_3") (pintype "passive"))
    )
    (net (code "122") (name "unconnected-(JP28-Pad4)") (class "Default")
      (node (ref "JP28") (pin "4") (pinfunction "4_4") (pintype "passive"))
    )
    (net (code "123") (name "unconnected-(JP28-Pad5)") (class "Default")
      (node (ref "JP28") (pin "5") (pinfunction "5_5") (pintype "passive"))
    )
    (net (code "124") (name "unconnected-(JP28-Pad6)") (class "Default")
      (node (ref "JP28") (pin "6") (pinfunction "6_6") (pintype "passive"))
    )
    (net (code "125") (name "unconnected-(JP28-Pad7)") (class "Default")
      (node (ref "JP28") (pin "7") (pinfunction "7_7") (pintype "passive"))
    )
    (net (code "126") (name "unconnected-(JP28-Pad8)") (class "Default")
      (node (ref "JP28") (pin "8") (pinfunction "8_8") (pintype "passive"))
    )
    (net (code "127") (name "unconnected-(JP28-Pad9)") (class "Default")
      (node (ref "JP28") (pin "9") (pinfunction "9_9") (pintype "passive"))
    )
    (net (code "128") (name "unconnected-(JP28-Pad10)") (class "Default")
      (node (ref "JP28") (pin "10") (pinfunction "10_10") (pintype "passive"))
    )
    (net (code "129") (name "unconnected-(JP29-Pad1)") (class "Default")
      (node (ref "JP29") (pin "1") (pinfunction "1_1") (pintype "passive"))
    )
    (net (code "130") (name "unconnected-(JP29-Pad2)") (class "Default")
      (node (ref "JP29") (pin "2") (pinfunction "2_2") (pintype "passive"))
    )
    (net (code "131") (name "unconnected-(JP29-Pad3)") (class "Default")
      (node (ref "JP29") (pin "3") (pinfunction "3_3") (pintype "passive"))
    )
    (net (code "132") (name "unconnected-(JP29-Pad4)") (class "Default")
      (node (ref "JP29") (pin "4") (pinfunction "4_4") (pintype "passive"))
    )
    (net (code "133") (name "unconnected-(JP29-Pad5)") (class "Default")
      (node (ref "JP29") (pin "5") (pinfunction "5_5") (pintype "passive"))
    )
    (net (code "134") (name "unconnected-(JP29-Pad6)") (class "Default")
      (node (ref "JP29") (pin "6") (pinfunction "6_6") (pintype "passive"))
    )
    (net (code "135") (name "unconnected-(JP29-Pad7)") (class "Default")
      (node (ref "JP29") (pin "7") (pinfunction "7_7") (pintype "passive"))
    )
    (net (code "136") (name "unconnected-(JP29-Pad8)") (class "Default")
      (node (ref "JP29") (pin "8") (pinfunction "8_8") (pintype "passive"))
    )
    (net (code "137") (name "unconnected-(JP30-Pad1)") (class "Default")
      (node (ref "JP30") (pin "1") (pinfunction "1_1") (pintype "passive"))
    )
    (net (code "138") (name "unconnected-(JP30-Pad2)") (class "Default")
      (node (ref "JP30") (pin "2") (pinfunction "2_2") (pintype "passive"))
    )
    (net (code "139") (name "unconnected-(JP30-Pad3)") (class "Default")
      (node (ref "JP30") (pin "3") (pinfunction "3_3") (pintype "passive"))
    )
    (net (code "140") (name "unconnected-(JP30-Pad4)") (class "Default")
      (node (ref "JP30") (pin "4") (pinfunction "4_4") (pintype "passive"))
    )
    (net (code "141") (name "unconnected-(JP30-Pad5)") (class "Default")
      (node (ref "JP30") (pin "5") (pinfunction "5_5") (pintype "passive"))
    )
    (net (code "142") (name "unconnected-(JP30-Pad6)") (class "Default")
      (node (ref "JP30") (pin "6") (pinfunction "6_6") (pintype "passive"))
    )
    (net (code "143") (name "unconnected-(JP30-Pad7)") (class "Default")
      (node (ref "JP30") (pin "7") (pinfunction "7_7") (pintype "passive"))
    )
    (net (code "144") (name "unconnected-(JP30-Pad8)") (class "Default")
      (node (ref "JP30") (pin "8") (pinfunction "8_8") (pintype "passive"))
    )
    (net (code "145") (name "unconnected-(JP31-Pad1)") (class "Default")
      (node (ref "JP31") (pin "1") (pinfunction "1_1") (pintype "passive"))
    )
    (net (code "146") (name "unconnected-(JP31-Pad2)") (class "Default")
      (node (ref "JP31") (pin "2") (pinfunction "2_2") (pintype "passive"))
    )
    (net (code "147") (name "unconnected-(JP31-Pad3)") (class "Default")
      (node (ref "JP31") (pin "3") (pinfunction "3_3") (pintype "passive"))
    )
    (net (code "148") (name "unconnected-(JP31-Pad4)") (class "Default")
      (node (ref "JP31") (pin "4") (pinfunction "4_4") (pintype "passive"))
    )
    (net (code "149") (name "unconnected-(JP31-Pad5)") (class "Default")
      (node (ref "JP31") (pin "5") (pinfunction "5_5") (pintype "passive"))
    )
    (net (code "150") (name "unconnected-(JP31-Pad6)") (class "Default")
      (node (ref "JP31") (pin "6") (pinfunction "6_6") (pintype "passive"))
    )
    (net (code "151") (name "unconnected-(JP31-Pad7)") (class "Default")
      (node (ref "JP31") (pin "7") (pinfunction "7_7") (pintype "passive"))
    )
    (net (code "152") (name "unconnected-(JP31-Pad8)") (class "Default")
      (node (ref "JP31") (pin "8") (pinfunction "8_8") (pintype "passive"))
    )
    (net (code "153") (name "unconnected-(JP32-Pad1)") (class "Default")
      (node (ref "JP32") (pin "1") (pinfunction "1_1") (pintype "passive"))
    )
    (net (code "154") (name "unconnected-(JP32-Pad2)") (class "Default")
      (node (ref "JP32") (pin "2") (pinfunction "2_2") (pintype "passive"))
    )
    (net (code "155") (name "unconnected-(JP32-Pad3)") (class "Default")
      (node (ref "JP32") (pin "3") (pinfunction "3_3") (pintype "passive"))
    )
    (net (code "156") (name "unconnected-(JP32-Pad4)") (class "Default")
      (node (ref "JP32") (pin "4") (pinfunction "4_4") (pintype "passive"))
    )
    (net (code "157") (name "unconnected-(JP32-Pad5)") (class "Default")
      (node (ref "JP32") (pin "5") (pinfunction "5_5") (pintype "passive"))
    )
    (net (code "158") (name "unconnected-(JP32-Pad6)") (class "Default")
      (node (ref "JP32") (pin "6") (pinfunction "6_6") (pintype "passive"))
    )
    (net (code "159") (name "unconnected-(JP32-Pad7)") (class "Default")
      (node (ref "JP32") (pin "7") (pinfunction "7_7") (pintype "passive"))
    )
    (net (code "160") (name "unconnected-(JP32-Pad8)") (class "Default")
      (node (ref "JP32") (pin "8") (pinfunction "8_8") (pintype "passive"))
    )
    (net (code "161") (name "unconnected-(JP33-Pad1)") (class "Default")
      (node (ref "JP33") (pin "1") (pinfunction "1_1") (pintype "passive"))
    )
    (net (code "162") (name "unconnected-(JP33-Pad2)") (class "Default")
      (node (ref "JP33") (pin "2") (pinfunction "2_2") (pintype "passive"))
    )
    (net (code "163") (name "unconnected-(JP33-Pad3)") (class "Default")
      (node (ref "JP33") (pin "3") (pinfunction "3_3") (pintype "passive"))
    )
    (net (code "164") (name "unconnected-(JP33-Pad4)") (class "Default")
      (node (ref "JP33") (pin "4") (pinfunction "4_4") (pintype "passive"))
    )
    (net (code "165") (name "unconnected-(JP33-Pad5)") (class "Default")
      (node (ref "JP33") (pin "5") (pinfunction "5_5") (pintype "passive"))
    )
    (net (code "166") (name "unconnected-(JP33-Pad6)") (class "Default")
      (node (ref "JP33") (pin "6") (pinfunction "6_6") (pintype "passive"))
    )
    (net (code "167") (name "unconnected-(JP33-Pad7)") (class "Default")
      (node (ref "JP33") (pin "7") (pinfunction "7_7") (pintype "passive"))
    )
    (net (code "168") (name "unconnected-(JP33-Pad8)") (class "Default")
      (node (ref "JP33") (pin "8") (pinfunction "8_8") (pintype "passive"))
    )
    (net (code "169") (name "unconnected-(JP33-Pad9)") (class "Default")
      (node (ref "JP33") (pin "9") (pinfunction "9_9") (pintype "passive"))
    )
    (net (code "170") (name "unconnected-(JP34-Pad1)") (class "Default")
      (node (ref "JP34") (pin "1") (pinfunction "1_1") (pintype "passive"))
    )
    (net (code "171") (name "unconnected-(JP34-Pad2)") (class "Default")
      (node (ref "JP34") (pin "2") (pinfunction "2_2") (pintype "passive"))
    )
    (net (code "172") (name "unconnected-(JP34-Pad3)") (class "Default")
      (node (ref "JP34") (pin "3") (pinfunction "3_3") (pintype "passive"))
    )
    (net (code "173") (name "unconnected-(JP34-Pad4)") (class "Default")
      (node (ref "JP34") (pin "4") (pinfunction "4_4") (pintype "passive"))
    )
    (net (code "174") (name "unconnected-(JP34-Pad5)") (class "Default")
      (node (ref "JP34") (pin "5") (pinfunction "5_5") (pintype "passive"))
    )
    (net (code "175") (name "unconnected-(JP34-Pad6)") (class "Default")
      (node (ref "JP34") (pin "6") (pinfunction "6_6") (pintype "passive"))
    )
    (net (code "176") (name "unconnected-(JP34-Pad7)") (class "Default")
      (node (ref "JP34") (pin "7") (pinfunction "7_7") (pintype "passive"))
    )
    (net (code "177") (name "unconnected-(JP34-Pad8)") (class "Default")
      (node (ref "JP34") (pin "8") (pinfunction "8_8") (pintype "passive"))
    )
    (net (code "178") (name "unconnected-(JP34-Pad9)") (class "Default")
      (node (ref "JP34") (pin "9") (pinfunction "9_9") (pintype "passive"))
    )
    (net (code "179") (name "unconnected-(JP35-Pad1)") (class "Default")
      (node (ref "JP35") (pin "1") (pinfunction "1_1") (pintype "passive"))
    )
    (net (code "180") (name "unconnected-(JP35-Pad2)") (class "Default")
      (node (ref "JP35") (pin "2") (pinfunction "2_2") (pintype "passive"))
    )
    (net (code "181") (name "unconnected-(JP35-Pad3)") (class "Default")
      (node (ref "JP35") (pin "3") (pinfunction "3_3") (pintype "passive"))
    )
    (net (code "182") (name "unconnected-(JP35-Pad4)") (class "Default")
      (node (ref "JP35") (pin "4") (pinfunction "4_4") (pintype "passive"))
    )
    (net (code "183") (name "unconnected-(JP35-Pad5)") (class "Default")
      (node (ref "JP35") (pin "5") (pinfunction "5_5") (pintype "passive"))
    )
    (net (code "184") (name "unconnected-(JP35-Pad6)") (class "Default")
      (node (ref "JP35") (pin "6") (pinfunction "6_6") (pintype "passive"))
    )
    (net (code "185") (name "unconnected-(JP35-Pad7)") (class "Default")
      (node (ref "JP35") (pin "7") (pinfunction "7_7") (pintype "passive"))
    )
    (net (code "186") (name "unconnected-(JP35-Pad8)") (class "Default")
      (node (ref "JP35") (pin "8") (pinfunction "8_8") (pintype "passive"))
    )
  )
)
